# SCH_PicoPU_MoBo_2025-06-30.net
KiCad netlist of a schematic drawn in EasyEDA
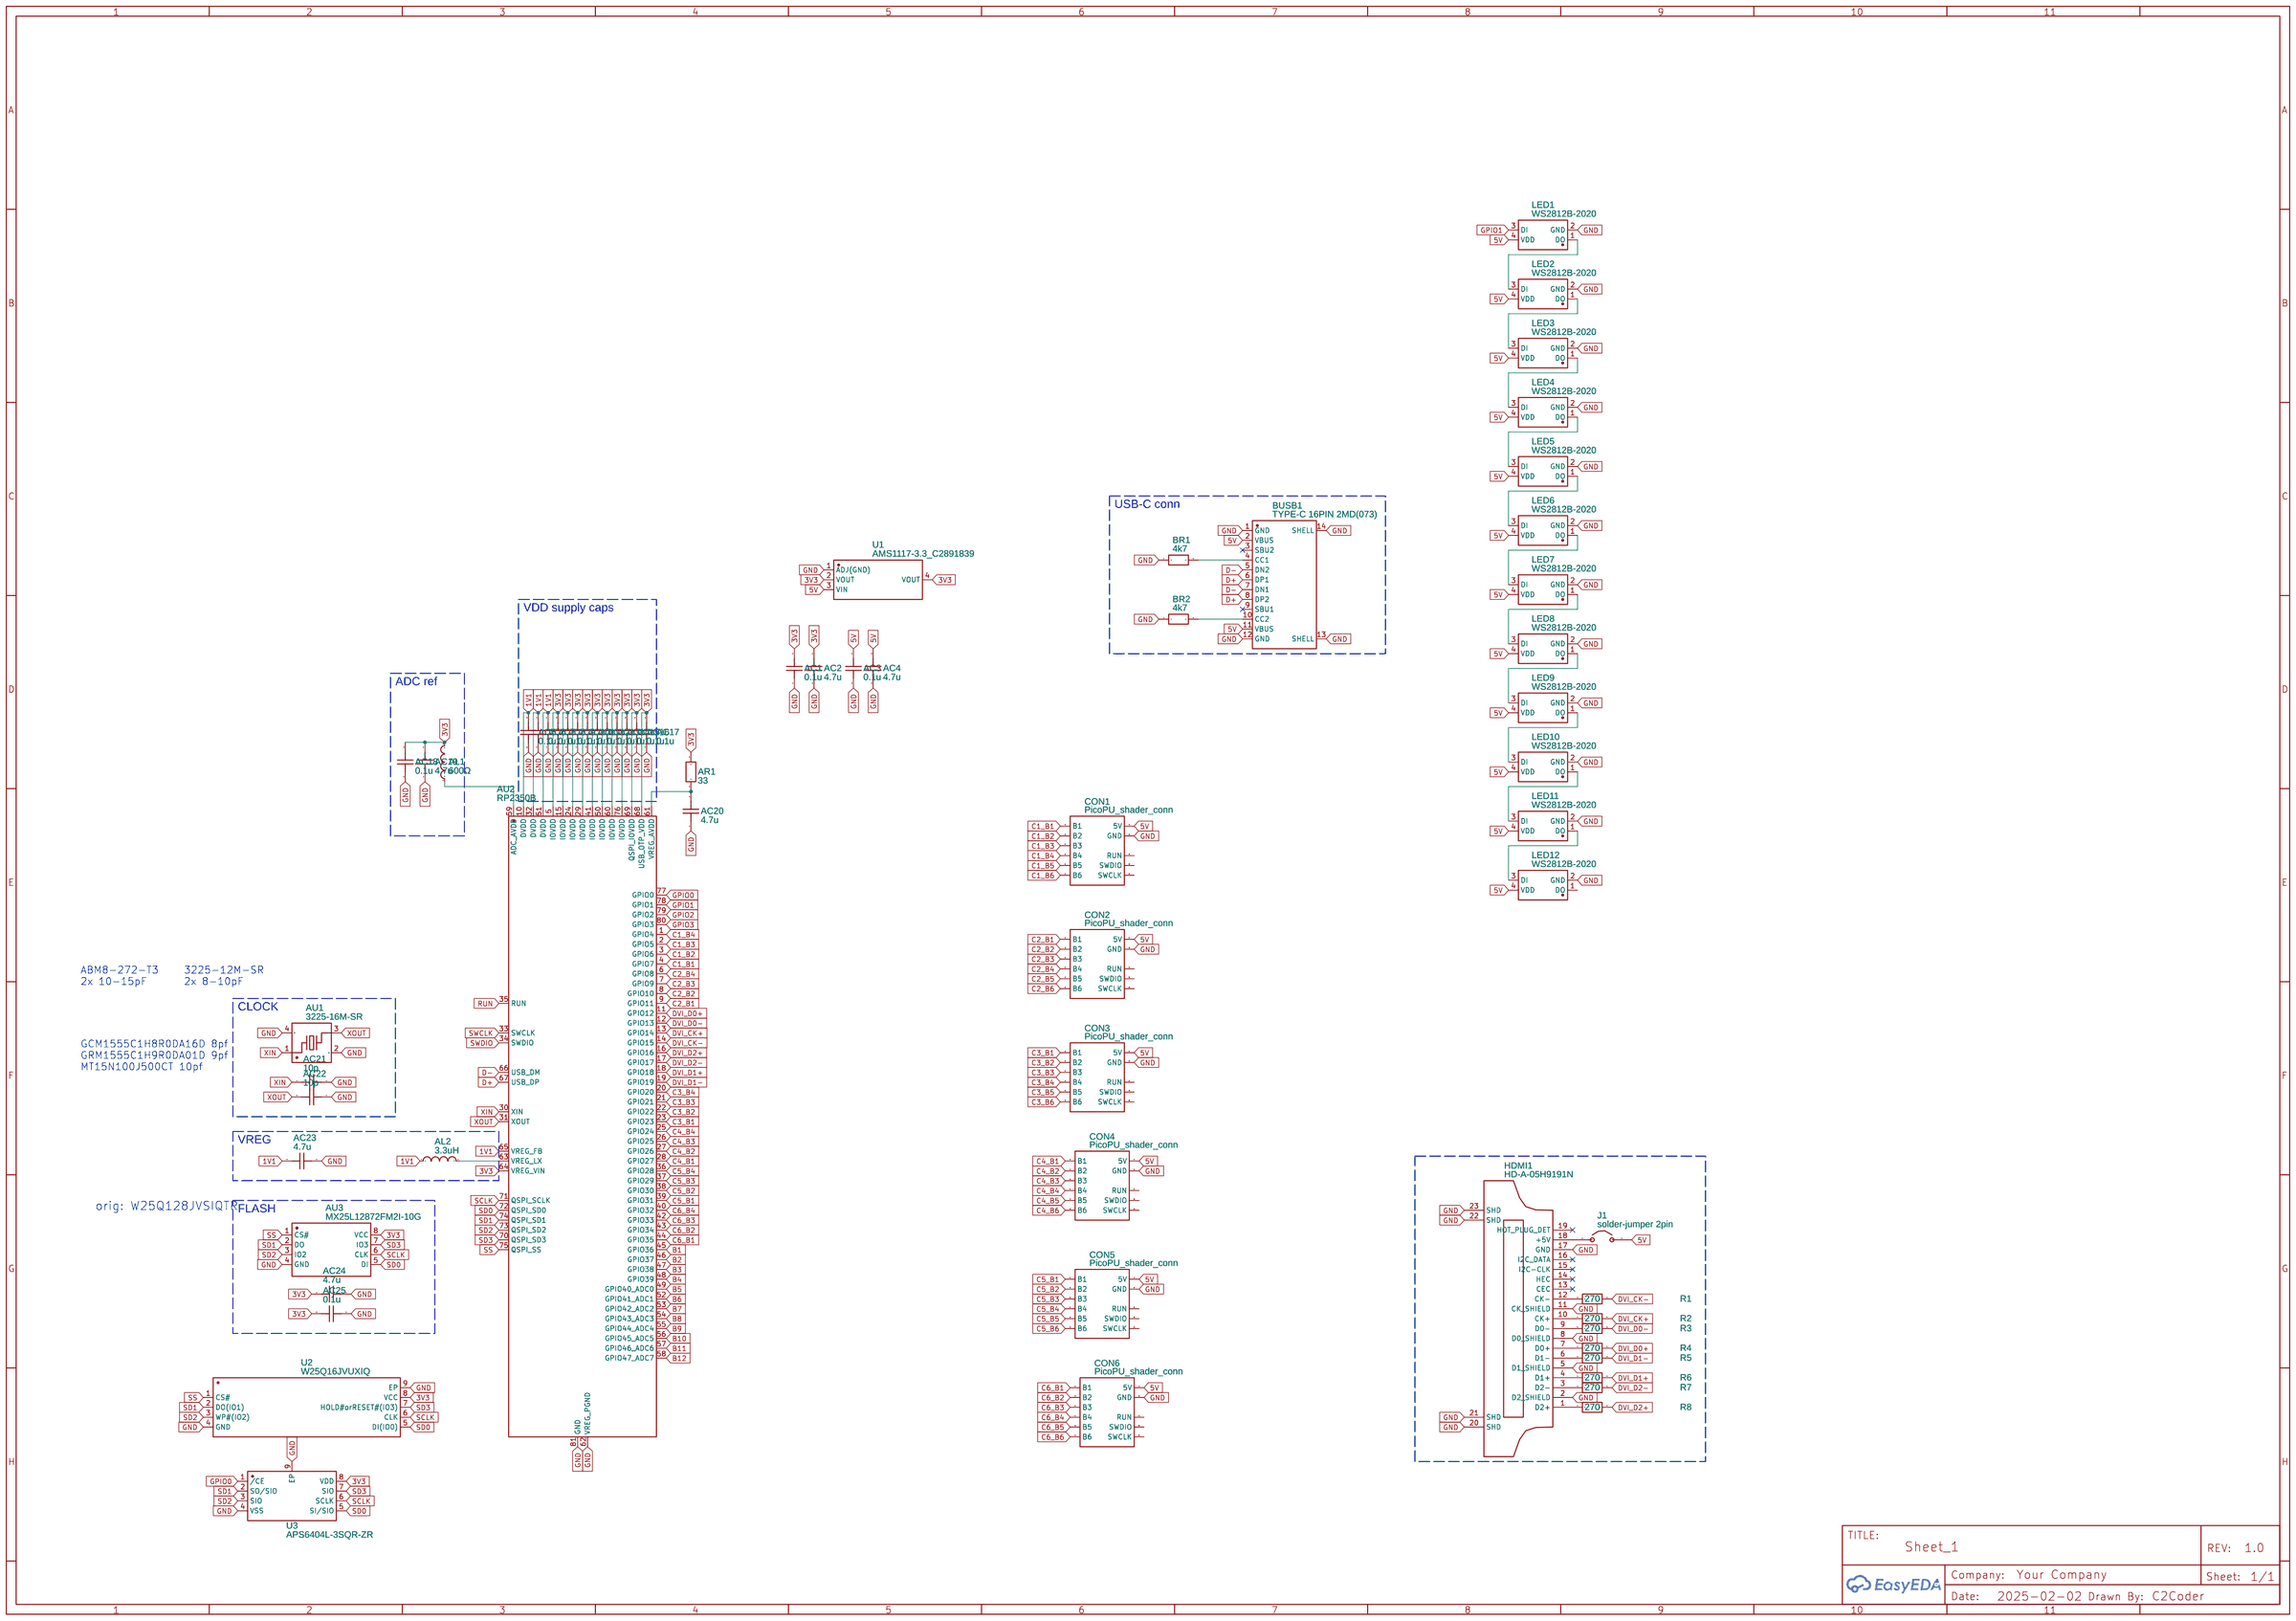
[diagram p0: schematic sheet]

(export (version "E")
  (design (tool "Eeschema 10.0.6"))
  (components
    (comp (ref "AC1")
      (value "0.1u")
      (fields (field (name "Manufacturer Part") "CL05B104KP5NNNC") (field (name "Manufacturer") "SAMSUNG"))
      (libsource (lib "") (part "C_0402_US"))
    )
    (comp (ref "AC2")
      (value "4.7u")
      (fields (field (name "Manufacturer Part") "0603X475K100CT") (field (name "Manufacturer") "WALSIN"))
      (libsource (lib "") (part "C_0402_US"))
    )
    (comp (ref "AC3")
      (value "0.1u")
      (fields (field (name "Manufacturer Part") "CL05B104KP5NNNC") (field (name "Manufacturer") "SAMSUNG"))
      (libsource (lib "") (part "C_0402_US"))
    )
    (comp (ref "AC4")
      (value "4.7u")
      (fields (field (name "Manufacturer Part") "0603X475K100CT") (field (name "Manufacturer") "WALSIN"))
      (libsource (lib "") (part "C_0402_US"))
    )
    (comp (ref "AC5")
      (value "0.1u")
      (fields (field (name "Manufacturer Part") "CL05B104KP5NNNC") (field (name "Manufacturer") "SAMSUNG"))
      (libsource (lib "") (part "C_0402_US"))
    )
    (comp (ref "AC6")
      (value "0.1u")
      (fields (field (name "Manufacturer Part") "CL05B104KP5NNNC") (field (name "Manufacturer") "SAMSUNG"))
      (libsource (lib "") (part "C_0402_US"))
    )
    (comp (ref "AC7")
      (value "0.1u")
      (fields (field (name "Manufacturer Part") "CL05B104KP5NNNC") (field (name "Manufacturer") "SAMSUNG"))
      (libsource (lib "") (part "C_0402_US"))
    )
    (comp (ref "AC8")
      (value "0.1u")
      (fields (field (name "Manufacturer Part") "CL05B104KP5NNNC") (field (name "Manufacturer") "SAMSUNG"))
      (libsource (lib "") (part "C_0402_US"))
    )
    (comp (ref "AC9")
      (value "0.1u")
      (fields (field (name "Manufacturer Part") "CL05B104KP5NNNC") (field (name "Manufacturer") "SAMSUNG"))
      (libsource (lib "") (part "C_0402_US"))
    )
    (comp (ref "AC10")
      (value "0.1u")
      (fields (field (name "Manufacturer Part") "CL05B104KP5NNNC") (field (name "Manufacturer") "SAMSUNG"))
      (libsource (lib "") (part "C_0402_US"))
    )
    (comp (ref "AC11")
      (value "0.1u")
      (fields (field (name "Manufacturer Part") "CL05B104KP5NNNC") (field (name "Manufacturer") "SAMSUNG"))
      (libsource (lib "") (part "C_0402_US"))
    )
    (comp (ref "AC12")
      (value "0.1u")
      (fields (field (name "Manufacturer Part") "CL05B104KP5NNNC") (field (name "Manufacturer") "SAMSUNG"))
      (libsource (lib "") (part "C_0402_US"))
    )
    (comp (ref "AC13")
      (value "0.1u")
      (fields (field (name "Manufacturer Part") "CL05B104KP5NNNC") (field (name "Manufacturer") "SAMSUNG"))
      (libsource (lib "") (part "C_0402_US"))
    )
    (comp (ref "AC14")
      (value "0.1u")
      (fields (field (name "Manufacturer Part") "CL05B104KP5NNNC") (field (name "Manufacturer") "SAMSUNG"))
      (libsource (lib "") (part "C_0402_US"))
    )
    (comp (ref "AC15")
      (value "0.1u")
      (fields (field (name "Manufacturer Part") "CL05B104KP5NNNC") (field (name "Manufacturer") "SAMSUNG"))
      (libsource (lib "") (part "C_0402_US"))
    )
    (comp (ref "AC16")
      (value "0.1u")
      (fields (field (name "Manufacturer Part") "CL05B104KP5NNNC") (field (name "Manufacturer") "SAMSUNG"))
      (libsource (lib "") (part "C_0402_US"))
    )
    (comp (ref "AC17")
      (value "0.1u")
      (fields (field (name "Manufacturer Part") "CL05B104KP5NNNC") (field (name "Manufacturer") "SAMSUNG"))
      (libsource (lib "") (part "C_0402_US"))
    )
    (comp (ref "AC18")
      (value "0.1u")
      (fields (field (name "Manufacturer Part") "CL05B104KP5NNNC") (field (name "Manufacturer") "SAMSUNG"))
      (libsource (lib "") (part "C_0402_US"))
    )
    (comp (ref "AC19")
      (value "4.7u")
      (fields (field (name "Manufacturer Part") "0603X475K100CT") (field (name "Manufacturer") "WALSIN"))
      (libsource (lib "") (part "C_0402_US"))
    )
    (comp (ref "AC20")
      (value "4.7u")
      (fields (field (name "Manufacturer Part") "0603X475K100CT") (field (name "Manufacturer") "WALSIN"))
      (libsource (lib "") (part "C_0402_US"))
    )
    (comp (ref "AC21")
      (value "10p")
      (fields (field (name "Manufacturer Part") "MT15N100J500CT") (field (name "Manufacturer") "WALSIN"))
      (libsource (lib "") (part "C_0402_US_1"))
    )
    (comp (ref "AC22")
      (value "10p")
      (fields (field (name "Manufacturer Part") "MT15N100J500CT") (field (name "Manufacturer") "WALSIN"))
      (libsource (lib "") (part "C_0402_US_1"))
    )
    (comp (ref "AC23")
      (value "4.7u")
      (fields (field (name "Manufacturer Part") "0603X475K100CT") (field (name "Manufacturer") "WALSIN"))
      (libsource (lib "") (part "C_0402_US_1"))
    )
    (comp (ref "AC24")
      (value "4.7u")
      (fields (field (name "Manufacturer Part") "0603X475K100CT") (field (name "Manufacturer") "WALSIN"))
      (libsource (lib "") (part "C_0402_US_1"))
    )
    (comp (ref "AC25")
      (value "0.1u")
      (fields (field (name "Manufacturer Part") "CL05B104KP5NNNC") (field (name "Manufacturer") "SAMSUNG"))
      (libsource (lib "") (part "C_0402_US_1"))
    )
    (comp (ref "AL1")
      (value "600Ω")
      (fields (field (name "Manufacturer Part") "BLM18HE601SN1D") (field (name "Manufacturer") "muRata"))
      (libsource (lib "") (part "BLM18HE601SN1D"))
    )
    (comp (ref "AL2")
      (value "3.3uH")
      (fields (field (name "Manufacturer Part") "LQM2HPN3R3MG0L") (field (name "Manufacturer") "MURATA"))
      (libsource (lib "") (part "AOTA-B201610S3R3-101-T"))
    )
    (comp (ref "AR1")
      (value "33")
      (fields (field (name "Manufacturer Part") "HP02WAF330JTCE") (field (name "Manufacturer") "ROYALOHM"))
      (libsource (lib "") (part "R_0402_EU_2"))
    )
    (comp (ref "AU1")
      (value "3225-16M-SR")
      (fields (field (name "Manufacturer") "SR Passives"))
      (libsource (lib "") (part "3225-16M-SR"))
    )
    (comp (ref "AU2") (value "RP2350B") (libsource (lib "") (part "RP2350B")))
    (comp (ref "AU3")
      (value "MX25L12872FM2I-10G")
      (fields (field (name "Manufacturer Part") "AT25SF081B-SSHD-T") (field (name "Manufacturer") "RENESAS"))
      (libsource (lib "") (part "W25Q128JVSIQTR"))
    )
    (comp (ref "BR1")
      (value "4k7")
      (fields (field (name "Manufacturer Part") "HP02WAF4701TCE") (field (name "Manufacturer") "ROYALOHM"))
      (libsource (lib "") (part "R_0402_EU_1"))
    )
    (comp (ref "BR2")
      (value "4k7")
      (fields (field (name "Manufacturer Part") "HP02WAF4701TCE") (field (name "Manufacturer") "ROYALOHM"))
      (libsource (lib "") (part "R_0402_EU_1"))
    )
    (comp (ref "BUSB1")
      (value "TYPE-C 16PIN 2MD(073)")
      (fields (field (name "Manufacturer Part") "USB4215-03-A") (field (name "Manufacturer") "GCT"))
      (libsource (lib "") (part "TYPE-C 16PIN 2MD(073)"))
    )
    (comp (ref "CON1") (value "PicoPU_shader_conn") (libsource (lib "") (part "PicoPU_shader_conn")))
    (comp (ref "CON2") (value "PicoPU_shader_conn") (libsource (lib "") (part "PicoPU_shader_conn")))
    (comp (ref "CON3") (value "PicoPU_shader_conn") (libsource (lib "") (part "PicoPU_shader_conn")))
    (comp (ref "CON4") (value "PicoPU_shader_conn") (libsource (lib "") (part "PicoPU_shader_conn")))
    (comp (ref "CON5") (value "PicoPU_shader_conn") (libsource (lib "") (part "PicoPU_shader_conn")))
    (comp (ref "CON6") (value "PicoPU_shader_conn") (libsource (lib "") (part "PicoPU_shader_conn")))
    (comp (ref "HDMI1")
      (value "HD-A-05H9191N")
      (fields (field (name "Manufacturer") "HanElectricity(瀚源)"))
      (libsource (lib "") (part "HD-A-05H9191N"))
    )
    (comp (ref "J1") (value "solder-jumper 2pin") (libsource (lib "") (part "solder-jumper 2pin")))
    (comp (ref "LED1")
      (value "WS2812B-2020")
      (fields (field (name "Manufacturer") "worldsemi"))
      (libsource (lib "") (part "WS2812B-2020"))
    )
    (comp (ref "LED2")
      (value "WS2812B-2020")
      (fields (field (name "Manufacturer") "worldsemi"))
      (libsource (lib "") (part "WS2812B-2020"))
    )
    (comp (ref "LED3")
      (value "WS2812B-2020")
      (fields (field (name "Manufacturer") "worldsemi"))
      (libsource (lib "") (part "WS2812B-2020"))
    )
    (comp (ref "LED4")
      (value "WS2812B-2020")
      (fields (field (name "Manufacturer") "worldsemi"))
      (libsource (lib "") (part "WS2812B-2020"))
    )
    (comp (ref "LED5")
      (value "WS2812B-2020")
      (fields (field (name "Manufacturer") "worldsemi"))
      (libsource (lib "") (part "WS2812B-2020"))
    )
    (comp (ref "LED6")
      (value "WS2812B-2020")
      (fields (field (name "Manufacturer") "worldsemi"))
      (libsource (lib "") (part "WS2812B-2020"))
    )
    (comp (ref "LED7")
      (value "WS2812B-2020")
      (fields (field (name "Manufacturer") "worldsemi"))
      (libsource (lib "") (part "WS2812B-2020"))
    )
    (comp (ref "LED8")
      (value "WS2812B-2020")
      (fields (field (name "Manufacturer") "worldsemi"))
      (libsource (lib "") (part "WS2812B-2020"))
    )
    (comp (ref "LED9")
      (value "WS2812B-2020")
      (fields (field (name "Manufacturer") "worldsemi"))
      (libsource (lib "") (part "WS2812B-2020"))
    )
    (comp (ref "LED10")
      (value "WS2812B-2020")
      (fields (field (name "Manufacturer") "worldsemi"))
      (libsource (lib "") (part "WS2812B-2020"))
    )
    (comp (ref "LED11")
      (value "WS2812B-2020")
      (fields (field (name "Manufacturer") "worldsemi"))
      (libsource (lib "") (part "WS2812B-2020"))
    )
    (comp (ref "LED12")
      (value "WS2812B-2020")
      (fields (field (name "Manufacturer") "worldsemi"))
      (libsource (lib "") (part "WS2812B-2020"))
    )
    (comp (ref "R1") (value "270") (libsource (lib "") (part "R_0402_EU")))
    (comp (ref "R2") (value "270") (libsource (lib "") (part "R_0402_EU")))
    (comp (ref "R3") (value "270") (libsource (lib "") (part "R_0402_EU")))
    (comp (ref "R4") (value "270") (libsource (lib "") (part "R_0402_EU")))
    (comp (ref "R5") (value "270") (libsource (lib "") (part "R_0402_EU")))
    (comp (ref "R6") (value "270") (libsource (lib "") (part "R_0402_EU")))
    (comp (ref "R7") (value "270") (libsource (lib "") (part "R_0402_EU")))
    (comp (ref "R8") (value "270") (libsource (lib "") (part "R_0402_EU")))
    (comp (ref "U1")
      (value "AMS1117-3.3_C2891839")
      (fields (field (name "Manufacturer Part") "AMS1117-3.3") (field (name "Manufacturer") "YONGYUTAI(永裕泰)"))
      (libsource (lib "") (part "AMS1117-3.3_C2891839"))
    )
    (comp (ref "U2")
      (value "W25Q16JVUXIQ")
      (fields (field (name "Manufacturer") "WINBOND(华邦)"))
      (libsource (lib "") (part "W25Q16JVUXIQ"))
    )
    (comp (ref "U3")
      (value "APS6404L-3SQR-ZR")
      (fields (field (name "Manufacturer") "Apmemory"))
      (libsource (lib "") (part "APS6404L-3SQR-ZR"))
    )
  )
  (nets
    (net (code "1") (name "1V1") (class "Default")
      (node (ref "AC23") (pin "2") (pinfunction "2_2") (pintype "unspecified"))
      (node (ref "AC5") (pin "2") (pinfunction "2_2") (pintype "unspecified"))
      (node (ref "AC6") (pin "2") (pinfunction "2_2") (pintype "unspecified"))
      (node (ref "AC7") (pin "2") (pinfunction "2_2") (pintype "unspecified"))
      (node (ref "AL2") (pin "1") (pinfunction "1_1") (pintype "unspecified"))
      (node (ref "AU2") (pin "10") (pinfunction "DVDD_10") (pintype "unspecified"))
      (node (ref "AU2") (pin "32") (pinfunction "DVDD_32") (pintype "unspecified"))
      (node (ref "AU2") (pin "51") (pinfunction "DVDD_51") (pintype "unspecified"))
      (node (ref "AU2") (pin "65") (pinfunction "VREG_FB_65") (pintype "unspecified"))
    )
    (net (code "2") (name "3V3") (class "Default")
      (node (ref "AC1") (pin "2") (pinfunction "2_2") (pintype "unspecified"))
      (node (ref "AC10") (pin "2") (pinfunction "2_2") (pintype "unspecified"))
      (node (ref "AC11") (pin "2") (pinfunction "2_2") (pintype "unspecified"))
      (node (ref "AC12") (pin "2") (pinfunction "2_2") (pintype "unspecified"))
      (node (ref "AC13") (pin "2") (pinfunction "2_2") (pintype "unspecified"))
      (node (ref "AC14") (pin "2") (pinfunction "2_2") (pintype "unspecified"))
      (node (ref "AC15") (pin "2") (pinfunction "2_2") (pintype "unspecified"))
      (node (ref "AC16") (pin "2") (pinfunction "2_2") (pintype "unspecified"))
      (node (ref "AC17") (pin "2") (pinfunction "2_2") (pintype "unspecified"))
      (node (ref "AC18") (pin "2") (pinfunction "2_2") (pintype "unspecified"))
      (node (ref "AC19") (pin "2") (pinfunction "2_2") (pintype "unspecified"))
      (node (ref "AC2") (pin "2") (pinfunction "2_2") (pintype "unspecified"))
      (node (ref "AC24") (pin "2") (pinfunction "2_2") (pintype "unspecified"))
      (node (ref "AC25") (pin "2") (pinfunction "2_2") (pintype "unspecified"))
      (node (ref "AC8") (pin "2") (pinfunction "2_2") (pintype "unspecified"))
      (node (ref "AC9") (pin "2") (pinfunction "2_2") (pintype "unspecified"))
      (node (ref "AL1") (pin "2") (pinfunction "2_2") (pintype "unspecified"))
      (node (ref "AR1") (pin "2") (pinfunction "2_2") (pintype "unspecified"))
      (node (ref "AU2") (pin "15") (pinfunction "IOVDD_15") (pintype "unspecified"))
      (node (ref "AU2") (pin "24") (pinfunction "IOVDD_24") (pintype "unspecified"))
      (node (ref "AU2") (pin "29") (pinfunction "IOVDD_29") (pintype "unspecified"))
      (node (ref "AU2") (pin "41") (pinfunction "IOVDD_41") (pintype "unspecified"))
      (node (ref "AU2") (pin "5") (pinfunction "IOVDD_5") (pintype "unspecified"))
      (node (ref "AU2") (pin "50") (pinfunction "IOVDD_50") (pintype "unspecified"))
      (node (ref "AU2") (pin "60") (pinfunction "IOVDD_60") (pintype "unspecified"))
      (node (ref "AU2") (pin "64") (pinfunction "VREG_VIN_64") (pintype "unspecified"))
      (node (ref "AU2") (pin "68") (pinfunction "USB_OTP_VDD_68") (pintype "unspecified"))
      (node (ref "AU2") (pin "69") (pinfunction "QSPI_IOVDD_69") (pintype "unspecified"))
      (node (ref "AU2") (pin "76") (pinfunction "IOVDD_76") (pintype "unspecified"))
      (node (ref "AU3") (pin "8") (pinfunction "VCC_8") (pintype "unspecified"))
      (node (ref "U1") (pin "2") (pinfunction "VOUT_2") (pintype "unspecified"))
      (node (ref "U1") (pin "4") (pinfunction "VOUT_4") (pintype "unspecified"))
      (node (ref "U2") (pin "8") (pinfunction "VCC_8") (pintype "unspecified"))
      (node (ref "U3") (pin "8") (pinfunction "VDD_8") (pintype "unspecified"))
    )
    (net (code "3") (name "5V") (class "Default")
      (node (ref "AC3") (pin "2") (pinfunction "2_2") (pintype "unspecified"))
      (node (ref "AC4") (pin "2") (pinfunction "2_2") (pintype "unspecified"))
      (node (ref "BUSB1") (pin "11") (pinfunction "VBUS_11") (pintype "unspecified"))
      (node (ref "BUSB1") (pin "2") (pinfunction "VBUS_2") (pintype "unspecified"))
      (node (ref "CON1") (pin "5V") (pinfunction "5V_5V") (pintype "unspecified"))
      (node (ref "CON2") (pin "5V") (pinfunction "5V_5V") (pintype "unspecified"))
      (node (ref "CON3") (pin "5V") (pinfunction "5V_5V") (pintype "unspecified"))
      (node (ref "CON4") (pin "5V") (pinfunction "5V_5V") (pintype "unspecified"))
      (node (ref "CON5") (pin "5V") (pinfunction "5V_5V") (pintype "unspecified"))
      (node (ref "CON6") (pin "5V") (pinfunction "5V_5V") (pintype "unspecified"))
      (node (ref "J1") (pin "2") (pinfunction "2_2") (pintype "unspecified"))
      (node (ref "LED1") (pin "4") (pinfunction "VDD_4") (pintype "unspecified"))
      (node (ref "LED10") (pin "4") (pinfunction "VDD_4") (pintype "unspecified"))
      (node (ref "LED11") (pin "4") (pinfunction "VDD_4") (pintype "unspecified"))
      (node (ref "LED12") (pin "4") (pinfunction "VDD_4") (pintype "unspecified"))
      (node (ref "LED2") (pin "4") (pinfunction "VDD_4") (pintype "unspecified"))
      (node (ref "LED3") (pin "4") (pinfunction "VDD_4") (pintype "unspecified"))
      (node (ref "LED4") (pin "4") (pinfunction "VDD_4") (pintype "unspecified"))
      (node (ref "LED5") (pin "4") (pinfunction "VDD_4") (pintype "unspecified"))
      (node (ref "LED6") (pin "4") (pinfunction "VDD_4") (pintype "unspecified"))
      (node (ref "LED7") (pin "4") (pinfunction "VDD_4") (pintype "unspecified"))
      (node (ref "LED8") (pin "4") (pinfunction "VDD_4") (pintype "unspecified"))
      (node (ref "LED9") (pin "4") (pinfunction "VDD_4") (pintype "unspecified"))
      (node (ref "U1") (pin "3") (pinfunction "VIN_3") (pintype "unspecified"))
    )
    (net (code "4") (name "B1") (class "Default")
      (node (ref "AU2") (pin "45") (pinfunction "GPIO36_45") (pintype "unspecified"))
    )
    (net (code "5") (name "B2") (class "Default")
      (node (ref "AU2") (pin "46") (pinfunction "GPIO37_46") (pintype "unspecified"))
    )
    (net (code "6") (name "B3") (class "Default")
      (node (ref "AU2") (pin "47") (pinfunction "GPIO38_47") (pintype "unspecified"))
    )
    (net (code "7") (name "B4") (class "Default")
      (node (ref "AU2") (pin "48") (pinfunction "GPIO39_48") (pintype "unspecified"))
    )
    (net (code "8") (name "B5") (class "Default")
      (node (ref "AU2") (pin "49") (pinfunction "GPIO40_ADC0_49") (pintype "unspecified"))
    )
    (net (code "9") (name "B6") (class "Default")
      (node (ref "AU2") (pin "52") (pinfunction "GPIO41_ADC1_52") (pintype "unspecified"))
    )
    (net (code "10") (name "B7") (class "Default")
      (node (ref "AU2") (pin "53") (pinfunction "GPIO42_ADC2_53") (pintype "unspecified"))
    )
    (net (code "11") (name "B8") (class "Default")
      (node (ref "AU2") (pin "54") (pinfunction "GPIO43_ADC3_54") (pintype "unspecified"))
    )
    (net (code "12") (name "B9") (class "Default")
      (node (ref "AU2") (pin "55") (pinfunction "GPIO44_ADC4_55") (pintype "unspecified"))
    )
    (net (code "13") (name "B10") (class "Default")
      (node (ref "AU2") (pin "56") (pinfunction "GPIO45_ADC5_56") (pintype "unspecified"))
    )
    (net (code "14") (name "B11") (class "Default")
      (node (ref "AU2") (pin "57") (pinfunction "GPIO46_ADC6_57") (pintype "unspecified"))
    )
    (net (code "15") (name "B12") (class "Default")
      (node (ref "AU2") (pin "58") (pinfunction "GPIO47_ADC7_58") (pintype "unspecified"))
    )
    (net (code "16") (name "C1_B1") (class "Default")
      (node (ref "AU2") (pin "4") (pinfunction "GPIO7_4") (pintype "unspecified"))
      (node (ref "CON1") (pin "B1") (pinfunction "B1_B1") (pintype "unspecified"))
    )
    (net (code "17") (name "C1_B2") (class "Default")
      (node (ref "AU2") (pin "3") (pinfunction "GPIO6_3") (pintype "unspecified"))
      (node (ref "CON1") (pin "B2") (pinfunction "B2_B2") (pintype "unspecified"))
    )
    (net (code "18") (name "C1_B3") (class "Default")
      (node (ref "AU2") (pin "2") (pinfunction "GPIO5_2") (pintype "unspecified"))
      (node (ref "CON1") (pin "B3") (pinfunction "B3_B3") (pintype "unspecified"))
    )
    (net (code "19") (name "C1_B4") (class "Default")
      (node (ref "AU2") (pin "1") (pinfunction "GPIO4_1") (pintype "unspecified"))
      (node (ref "CON1") (pin "B4") (pinfunction "B4_B4") (pintype "unspecified"))
    )
    (net (code "20") (name "C1_B5") (class "Default")
      (node (ref "CON1") (pin "B5") (pinfunction "B5_B5") (pintype "unspecified"))
    )
    (net (code "21") (name "C1_B6") (class "Default")
      (node (ref "CON1") (pin "B6") (pinfunction "B6_B6") (pintype "unspecified"))
    )
    (net (code "22") (name "C2_B1") (class "Default")
      (node (ref "AU2") (pin "9") (pinfunction "GPIO11_9") (pintype "unspecified"))
      (node (ref "CON2") (pin "B1") (pinfunction "B1_B1") (pintype "unspecified"))
    )
    (net (code "23") (name "C2_B2") (class "Default")
      (node (ref "AU2") (pin "8") (pinfunction "GPIO10_8") (pintype "unspecified"))
      (node (ref "CON2") (pin "B2") (pinfunction "B2_B2") (pintype "unspecified"))
    )
    (net (code "24") (name "C2_B3") (class "Default")
      (node (ref "AU2") (pin "7") (pinfunction "GPIO9_7") (pintype "unspecified"))
      (node (ref "CON2") (pin "B3") (pinfunction "B3_B3") (pintype "unspecified"))
    )
    (net (code "25") (name "C2_B4") (class "Default")
      (node (ref "AU2") (pin "6") (pinfunction "GPIO8_6") (pintype "unspecified"))
      (node (ref "CON2") (pin "B4") (pinfunction "B4_B4") (pintype "unspecified"))
    )
    (net (code "26") (name "C2_B5") (class "Default")
      (node (ref "CON2") (pin "B5") (pinfunction "B5_B5") (pintype "unspecified"))
    )
    (net (code "27") (name "C2_B6") (class "Default")
      (node (ref "CON2") (pin "B6") (pinfunction "B6_B6") (pintype "unspecified"))
    )
    (net (code "28") (name "C3_B1") (class "Default")
      (node (ref "AU2") (pin "23") (pinfunction "GPIO23_23") (pintype "unspecified"))
      (node (ref "CON3") (pin "B1") (pinfunction "B1_B1") (pintype "unspecified"))
    )
    (net (code "29") (name "C3_B2") (class "Default")
      (node (ref "AU2") (pin "22") (pinfunction "GPIO22_22") (pintype "unspecified"))
      (node (ref "CON3") (pin "B2") (pinfunction "B2_B2") (pintype "unspecified"))
    )
    (net (code "30") (name "C3_B3") (class "Default")
      (node (ref "AU2") (pin "21") (pinfunction "GPIO21_21") (pintype "unspecified"))
      (node (ref "CON3") (pin "B3") (pinfunction "B3_B3") (pintype "unspecified"))
    )
    (net (code "31") (name "C3_B4") (class "Default")
      (node (ref "AU2") (pin "20") (pinfunction "GPIO20_20") (pintype "unspecified"))
      (node (ref "CON3") (pin "B4") (pinfunction "B4_B4") (pintype "unspecified"))
    )
    (net (code "32") (name "C3_B5") (class "Default")
      (node (ref "CON3") (pin "B5") (pinfunction "B5_B5") (pintype "unspecified"))
    )
    (net (code "33") (name "C3_B6") (class "Default")
      (node (ref "CON3") (pin "B6") (pinfunction "B6_B6") (pintype "unspecified"))
    )
    (net (code "34") (name "C4_B1") (class "Default")
      (node (ref "AU2") (pin "28") (pinfunction "GPIO27_28") (pintype "unspecified"))
      (node (ref "CON4") (pin "B1") (pinfunction "B1_B1") (pintype "unspecified"))
    )
    (net (code "35") (name "C4_B2") (class "Default")
      (node (ref "AU2") (pin "27") (pinfunction "GPIO26_27") (pintype "unspecified"))
      (node (ref "CON4") (pin "B2") (pinfunction "B2_B2") (pintype "unspecified"))
    )
    (net (code "36") (name "C4_B3") (class "Default")
      (node (ref "AU2") (pin "26") (pinfunction "GPIO25_26") (pintype "unspecified"))
      (node (ref "CON4") (pin "B3") (pinfunction "B3_B3") (pintype "unspecified"))
    )
    (net (code "37") (name "C4_B4") (class "Default")
      (node (ref "AU2") (pin "25") (pinfunction "GPIO24_25") (pintype "unspecified"))
      (node (ref "CON4") (pin "B4") (pinfunction "B4_B4") (pintype "unspecified"))
    )
    (net (code "38") (name "C4_B5") (class "Default")
      (node (ref "CON4") (pin "B5") (pinfunction "B5_B5") (pintype "unspecified"))
    )
    (net (code "39") (name "C4_B6") (class "Default")
      (node (ref "CON4") (pin "B6") (pinfunction "B6_B6") (pintype "unspecified"))
    )
    (net (code "40") (name "C5_B1") (class "Default")
      (node (ref "AU2") (pin "39") (pinfunction "GPIO31_39") (pintype "unspecified"))
      (node (ref "CON5") (pin "B1") (pinfunction "B1_B1") (pintype "unspecified"))
    )
    (net (code "41") (name "C5_B2") (class "Default")
      (node (ref "AU2") (pin "38") (pinfunction "GPIO30_38") (pintype "unspecified"))
      (node (ref "CON5") (pin "B2") (pinfunction "B2_B2") (pintype "unspecified"))
    )
    (net (code "42") (name "C5_B3") (class "Default")
      (node (ref "AU2") (pin "37") (pinfunction "GPIO29_37") (pintype "unspecified"))
      (node (ref "CON5") (pin "B3") (pinfunction "B3_B3") (pintype "unspecified"))
    )
    (net (code "43") (name "C5_B4") (class "Default")
      (node (ref "AU2") (pin "36") (pinfunction "GPIO28_36") (pintype "unspecified"))
      (node (ref "CON5") (pin "B4") (pinfunction "B4_B4") (pintype "unspecified"))
    )
    (net (code "44") (name "C5_B5") (class "Default")
      (node (ref "CON5") (pin "B5") (pinfunction "B5_B5") (pintype "unspecified"))
    )
    (net (code "45") (name "C5_B6") (class "Default")
      (node (ref "CON5") (pin "B6") (pinfunction "B6_B6") (pintype "unspecified"))
    )
    (net (code "46") (name "C6_B1") (class "Default")
      (node (ref "AU2") (pin "44") (pinfunction "GPIO35_44") (pintype "unspecified"))
      (node (ref "CON6") (pin "B1") (pinfunction "B1_B1") (pintype "unspecified"))
    )
    (net (code "47") (name "C6_B2") (class "Default")
      (node (ref "AU2") (pin "43") (pinfunction "GPIO34_43") (pintype "unspecified"))
      (node (ref "CON6") (pin "B2") (pinfunction "B2_B2") (pintype "unspecified"))
    )
    (net (code "48") (name "C6_B3") (class "Default")
      (node (ref "AU2") (pin "42") (pinfunction "GPIO33_42") (pintype "unspecified"))
      (node (ref "CON6") (pin "B3") (pinfunction "B3_B3") (pintype "unspecified"))
    )
    (net (code "49") (name "C6_B4") (class "Default")
      (node (ref "AU2") (pin "40") (pinfunction "GPIO32_40") (pintype "unspecified"))
      (node (ref "CON6") (pin "B4") (pinfunction "B4_B4") (pintype "unspecified"))
    )
    (net (code "50") (name "C6_B5") (class "Default")
      (node (ref "CON6") (pin "B5") (pinfunction "B5_B5") (pintype "unspecified"))
    )
    (net (code "51") (name "C6_B6") (class "Default")
      (node (ref "CON6") (pin "B6") (pinfunction "B6_B6") (pintype "unspecified"))
    )
    (net (code "52") (name "D+") (class "Default")
      (node (ref "AU2") (pin "67") (pinfunction "USB_DP_67") (pintype "unspecified"))
      (node (ref "BUSB1") (pin "6") (pinfunction "DP1_6") (pintype "unspecified"))
      (node (ref "BUSB1") (pin "8") (pinfunction "DP2_8") (pintype "unspecified"))
    )
    (net (code "53") (name "D-") (class "Default")
      (node (ref "AU2") (pin "66") (pinfunction "USB_DM_66") (pintype "unspecified"))
      (node (ref "BUSB1") (pin "5") (pinfunction "DN2_5") (pintype "unspecified"))
      (node (ref "BUSB1") (pin "7") (pinfunction "DN1_7") (pintype "unspecified"))
    )
    (net (code "54") (name "DVI_CK+") (class "Default")
      (node (ref "AU2") (pin "13") (pinfunction "GPIO14_13") (pintype "unspecified"))
      (node (ref "R2") (pin "2") (pinfunction "2_2") (pintype "unspecified"))
    )
    (net (code "55") (name "DVI_CK-") (class "Default")
      (node (ref "AU2") (pin "14") (pinfunction "GPIO15_14") (pintype "unspecified"))
      (node (ref "R1") (pin "2") (pinfunction "2_2") (pintype "unspecified"))
    )
    (net (code "56") (name "DVI_D0+") (class "Default")
      (node (ref "AU2") (pin "11") (pinfunction "GPIO12_11") (pintype "unspecified"))
      (node (ref "R4") (pin "2") (pinfunction "2_2") (pintype "unspecified"))
    )
    (net (code "57") (name "DVI_D0-") (class "Default")
      (node (ref "AU2") (pin "12") (pinfunction "GPIO13_12") (pintype "unspecified"))
      (node (ref "R3") (pin "2") (pinfunction "2_2") (pintype "unspecified"))
    )
    (net (code "58") (name "DVI_D1+") (class "Default")
      (node (ref "AU2") (pin "18") (pinfunction "GPIO18_18") (pintype "unspecified"))
      (node (ref "R6") (pin "2") (pinfunction "2_2") (pintype "unspecified"))
    )
    (net (code "59") (name "DVI_D1-") (class "Default")
      (node (ref "AU2") (pin "19") (pinfunction "GPIO19_19") (pintype "unspecified"))
      (node (ref "R5") (pin "2") (pinfunction "2_2") (pintype "unspecified"))
    )
    (net (code "60") (name "DVI_D2+") (class "Default")
      (node (ref "AU2") (pin "16") (pinfunction "GPIO16_16") (pintype "unspecified"))
      (node (ref "R8") (pin "2") (pinfunction "2_2") (pintype "unspecified"))
    )
    (net (code "61") (name "DVI_D2-") (class "Default")
      (node (ref "AU2") (pin "17") (pinfunction "GPIO17_17") (pintype "unspecified"))
      (node (ref "R7") (pin "2") (pinfunction "2_2") (pintype "unspecified"))
    )
    (net (code "62") (name "GND") (class "Default")
      (node (ref "AC1") (pin "1") (pinfunction "1_1") (pintype "unspecified"))
      (node (ref "AC10") (pin "1") (pinfunction "1_1") (pintype "unspecified"))
      (node (ref "AC11") (pin "1") (pinfunction "1_1") (pintype "unspecified"))
      (node (ref "AC12") (pin "1") (pinfunction "1_1") (pintype "unspecified"))
      (node (ref "AC13") (pin "1") (pinfunction "1_1") (pintype "unspecified"))
      (node (ref "AC14") (pin "1") (pinfunction "1_1") (pintype "unspecified"))
      (node (ref "AC15") (pin "1") (pinfunction "1_1") (pintype "unspecified"))
      (node (ref "AC16") (pin "1") (pinfunction "1_1") (pintype "unspecified"))
      (node (ref "AC17") (pin "1") (pinfunction "1_1") (pintype "unspecified"))
      (node (ref "AC18") (pin "1") (pinfunction "1_1") (pintype "unspecified"))
      (node (ref "AC19") (pin "1") (pinfunction "1_1") (pintype "unspecified"))
      (node (ref "AC2") (pin "1") (pinfunction "1_1") (pintype "unspecified"))
      (node (ref "AC20") (pin "1") (pinfunction "1_1") (pintype "unspecified"))
      (node (ref "AC21") (pin "1") (pinfunction "1_1") (pintype "unspecified"))
      (node (ref "AC22") (pin "1") (pinfunction "1_1") (pintype "unspecified"))
      (node (ref "AC23") (pin "1") (pinfunction "1_1") (pintype "unspecified"))
      (node (ref "AC24") (pin "1") (pinfunction "1_1") (pintype "unspecified"))
      (node (ref "AC25") (pin "1") (pinfunction "1_1") (pintype "unspecified"))
      (node (ref "AC3") (pin "1") (pinfunction "1_1") (pintype "unspecified"))
      (node (ref "AC4") (pin "1") (pinfunction "1_1") (pintype "unspecified"))
      (node (ref "AC5") (pin "1") (pinfunction "1_1") (pintype "unspecified"))
      (node (ref "AC6") (pin "1") (pinfunction "1_1") (pintype "unspecified"))
      (node (ref "AC7") (pin "1") (pinfunction "1_1") (pintype "unspecified"))
      (node (ref "AC8") (pin "1") (pinfunction "1_1") (pintype "unspecified"))
      (node (ref "AC9") (pin "1") (pinfunction "1_1") (pintype "unspecified"))
      (node (ref "AU1") (pin "2") (pinfunction "GND_2") (pintype "input"))
      (node (ref "AU1") (pin "4") (pinfunction "GND_4") (pintype "input"))
      (node (ref "AU2") (pin "62") (pinfunction "VREG_PGND_62") (pintype "unspecified"))
      (node (ref "AU2") (pin "81") (pinfunction "GND_81") (pintype "unspecified"))
      (node (ref "AU3") (pin "4") (pinfunction "GND_4") (pintype "unspecified"))
      (node (ref "BR1") (pin "1") (pinfunction "1_1") (pintype "unspecified"))
      (node (ref "BR2") (pin "1") (pinfunction "1_1") (pintype "unspecified"))
      (node (ref "BUSB1") (pin "1") (pinfunction "GND_1") (pintype "unspecified"))
      (node (ref "BUSB1") (pin "12") (pinfunction "GND_12") (pintype "unspecified"))
      (node (ref "BUSB1") (pin "13") (pinfunction "SHELL_13") (pintype "unspecified"))
      (node (ref "BUSB1") (pin "14") (pinfunction "SHELL_14") (pintype "unspecified"))
      (node (ref "CON1") (pin "GND") (pinfunction "GND_GND") (pintype "unspecified"))
      (node (ref "CON2") (pin "GND") (pinfunction "GND_GND") (pintype "unspecified"))
      (node (ref "CON3") (pin "GND") (pinfunction "GND_GND") (pintype "unspecified"))
      (node (ref "CON4") (pin "GND") (pinfunction "GND_GND") (pintype "unspecified"))
      (node (ref "CON5") (pin "GND") (pinfunction "GND_GND") (pintype "unspecified"))
      (node (ref "CON6") (pin "GND") (pinfunction "GND_GND") (pintype "unspecified"))
      (node (ref "HDMI1") (pin "11") (pinfunction "CK_SHIELD_11") (pintype "unspecified"))
      (node (ref "HDMI1") (pin "17") (pinfunction "GND_17") (pintype "unspecified"))
      (node (ref "HDMI1") (pin "2") (pinfunction "D2_SHIELD_2") (pintype "unspecified"))
      (node (ref "HDMI1") (pin "20") (pinfunction "SHD_20") (pintype "unspecified"))
      (node (ref "HDMI1") (pin "21") (pinfunction "SHD_21") (pintype "unspecified"))
      (node (ref "HDMI1") (pin "22") (pinfunction "SHD_22") (pintype "unspecified"))
      (node (ref "HDMI1") (pin "23") (pinfunction "SHD_23") (pintype "unspecified"))
      (node (ref "HDMI1") (pin "5") (pinfunction "D1_SHIELD_5") (pintype "unspecified"))
      (node (ref "HDMI1") (pin "8") (pinfunction "D0_SHIELD_8") (pintype "unspecified"))
      (node (ref "LED1") (pin "2") (pinfunction "GND_2") (pintype "unspecified"))
      (node (ref "LED10") (pin "2") (pinfunction "GND_2") (pintype "unspecified"))
      (node (ref "LED11") (pin "2") (pinfunction "GND_2") (pintype "unspecified"))
      (node (ref "LED12") (pin "2") (pinfunction "GND_2") (pintype "unspecified"))
      (node (ref "LED2") (pin "2") (pinfunction "GND_2") (pintype "unspecified"))
      (node (ref "LED3") (pin "2") (pinfunction "GND_2") (pintype "unspecified"))
      (node (ref "LED4") (pin "2") (pinfunction "GND_2") (pintype "unspecified"))
      (node (ref "LED5") (pin "2") (pinfunction "GND_2") (pintype "unspecified"))
      (node (ref "LED6") (pin "2") (pinfunction "GND_2") (pintype "unspecified"))
      (node (ref "LED7") (pin "2") (pinfunction "GND_2") (pintype "unspecified"))
      (node (ref "LED8") (pin "2") (pinfunction "GND_2") (pintype "unspecified"))
      (node (ref "LED9") (pin "2") (pinfunction "GND_2") (pintype "unspecified"))
      (node (ref "U1") (pin "1") (pinfunction "ADJ(GND)_1") (pintype "unspecified"))
      (node (ref "U2") (pin "4") (pinfunction "GND_4") (pintype "unspecified"))
      (node (ref "U2") (pin "9") (pinfunction "EP_9") (pintype "unspecified"))
      (node (ref "U3") (pin "4") (pinfunction "VSS_4") (pintype "unspecified"))
      (node (ref "U3") (pin "9") (pinfunction "EP_9") (pintype "unspecified"))
    )
    (net (code "63") (name "GPIO0") (class "Default")
      (node (ref "AU2") (pin "77") (pinfunction "GPIO0_77") (pintype "unspecified"))
      (node (ref "U3") (pin "1") (pinfunction "/CE_1") (pintype "unspecified"))
    )
    (net (code "64") (name "GPIO1") (class "Default")
      (node (ref "AU2") (pin "78") (pinfunction "GPIO1_78") (pintype "unspecified"))
      (node (ref "LED1") (pin "3") (pinfunction "DI_3") (pintype "unspecified"))
    )
    (net (code "65") (name "GPIO2") (class "Default")
      (node (ref "AU2") (pin "79") (pinfunction "GPIO2_79") (pintype "unspecified"))
    )
    (net (code "66") (name "GPIO3") (class "Default")
      (node (ref "AU2") (pin "80") (pinfunction "GPIO3_80") (pintype "unspecified"))
    )
    (net (code "67") (name "Net-(AU2-ADC_AVDD)") (class "Default")
      (node (ref "AL1") (pin "1") (pinfunction "1_1") (pintype "unspecified"))
      (node (ref "AU2") (pin "59") (pinfunction "ADC_AVDD_59") (pintype "unspecified"))
    )
    (net (code "68") (name "Net-(AU2-VREG_AVDD)") (class "Default")
      (node (ref "AC20") (pin "2") (pinfunction "2_2") (pintype "unspecified"))
      (node (ref "AR1") (pin "1") (pinfunction "1_1") (pintype "unspecified"))
      (node (ref "AU2") (pin "61") (pinfunction "VREG_AVDD_61") (pintype "unspecified"))
    )
    (net (code "69") (name "Net-(AU2-VREG_LX)") (class "Default")
      (node (ref "AL2") (pin "2") (pinfunction "2_2") (pintype "unspecified"))
      (node (ref "AU2") (pin "63") (pinfunction "VREG_LX_63") (pintype "unspecified"))
    )
    (net (code "70") (name "Net-(BUSB1-CC1)") (class "Default")
      (node (ref "BR1") (pin "2") (pinfunction "2_2") (pintype "unspecified"))
      (node (ref "BUSB1") (pin "4") (pinfunction "CC1_4") (pintype "unspecified"))
    )
    (net (code "71") (name "Net-(BUSB1-CC2)") (class "Default")
      (node (ref "BR2") (pin "2") (pinfunction "2_2") (pintype "unspecified"))
      (node (ref "BUSB1") (pin "10") (pinfunction "CC2_10") (pintype "unspecified"))
    )
    (net (code "72") (name "Net-(HDMI1-+5V)") (class "Default")
      (node (ref "HDMI1") (pin "18") (pinfunction "+5V_18") (pintype "unspecified"))
      (node (ref "J1") (pin "1") (pinfunction "1_1") (pintype "unspecified"))
    )
    (net (code "73") (name "Net-(HDMI1-CK+)") (class "Default")
      (node (ref "HDMI1") (pin "10") (pinfunction "CK+_10") (pintype "unspecified"))
      (node (ref "R2") (pin "1") (pinfunction "1_1") (pintype "unspecified"))
    )
    (net (code "74") (name "Net-(HDMI1-CK-)") (class "Default")
      (node (ref "HDMI1") (pin "12") (pinfunction "CK-_12") (pintype "unspecified"))
      (node (ref "R1") (pin "1") (pinfunction "1_1") (pintype "unspecified"))
    )
    (net (code "75") (name "Net-(HDMI1-D0+)") (class "Default")
      (node (ref "HDMI1") (pin "7") (pinfunction "D0+_7") (pintype "unspecified"))
      (node (ref "R4") (pin "1") (pinfunction "1_1") (pintype "unspecified"))
    )
    (net (code "76") (name "Net-(HDMI1-D0-)") (class "Default")
      (node (ref "HDMI1") (pin "9") (pinfunction "D0-_9") (pintype "unspecified"))
      (node (ref "R3") (pin "1") (pinfunction "1_1") (pintype "unspecified"))
    )
    (net (code "77") (name "Net-(HDMI1-D1+)") (class "Default")
      (node (ref "HDMI1") (pin "4") (pinfunction "D1+_4") (pintype "unspecified"))
      (node (ref "R6") (pin "1") (pinfunction "1_1") (pintype "unspecified"))
    )
    (net (code "78") (name "Net-(HDMI1-D1-)") (class "Default")
      (node (ref "HDMI1") (pin "6") (pinfunction "D1-_6") (pintype "unspecified"))
      (node (ref "R5") (pin "1") (pinfunction "1_1") (pintype "unspecified"))
    )
    (net (code "79") (name "Net-(HDMI1-D2+)") (class "Default")
      (node (ref "HDMI1") (pin "1") (pinfunction "D2+_1") (pintype "unspecified"))
      (node (ref "R8") (pin "1") (pinfunction "1_1") (pintype "unspecified"))
    )
    (net (code "80") (name "Net-(HDMI1-D2-)") (class "Default")
      (node (ref "HDMI1") (pin "3") (pinfunction "D2-_3") (pintype "unspecified"))
      (node (ref "R7") (pin "1") (pinfunction "1_1") (pintype "unspecified"))
    )
    (net (code "81") (name "Net-(LED1-DO)") (class "Default")
      (node (ref "LED1") (pin "1") (pinfunction "DO_1") (pintype "unspecified"))
      (node (ref "LED2") (pin "3") (pinfunction "DI_3") (pintype "unspecified"))
    )
    (net (code "82") (name "Net-(LED2-DO)") (class "Default")
      (node (ref "LED2") (pin "1") (pinfunction "DO_1") (pintype "unspecified"))
      (node (ref "LED3") (pin "3") (pinfunction "DI_3") (pintype "unspecified"))
    )
    (net (code "83") (name "Net-(LED3-DO)") (class "Default")
      (node (ref "LED3") (pin "1") (pinfunction "DO_1") (pintype "unspecified"))
      (node (ref "LED4") (pin "3") (pinfunction "DI_3") (pintype "unspecified"))
    )
    (net (code "84") (name "Net-(LED4-DO)") (class "Default")
      (node (ref "LED4") (pin "1") (pinfunction "DO_1") (pintype "unspecified"))
      (node (ref "LED5") (pin "3") (pinfunction "DI_3") (pintype "unspecified"))
    )
    (net (code "85") (name "Net-(LED5-DO)") (class "Default")
      (node (ref "LED5") (pin "1") (pinfunction "DO_1") (pintype "unspecified"))
      (node (ref "LED6") (pin "3") (pinfunction "DI_3") (pintype "unspecified"))
    )
    (net (code "86") (name "Net-(LED6-DO)") (class "Default")
      (node (ref "LED6") (pin "1") (pinfunction "DO_1") (pintype "unspecified"))
      (node (ref "LED7") (pin "3") (pinfunction "DI_3") (pintype "unspecified"))
    )
    (net (code "87") (name "Net-(LED7-DO)") (class "Default")
      (node (ref "LED7") (pin "1") (pinfunction "DO_1") (pintype "unspecified"))
      (node (ref "LED8") (pin "3") (pinfunction "DI_3") (pintype "unspecified"))
    )
    (net (code "88") (name "Net-(LED8-DO)") (class "Default")
      (node (ref "LED8") (pin "1") (pinfunction "DO_1") (pintype "unspecified"))
      (node (ref "LED9") (pin "3") (pinfunction "DI_3") (pintype "unspecified"))
    )
    (net (code "89") (name "Net-(LED10-DI)") (class "Default")
      (node (ref "LED10") (pin "3") (pinfunction "DI_3") (pintype "unspecified"))
      (node (ref "LED9") (pin "1") (pinfunction "DO_1") (pintype "unspecified"))
    )
    (net (code "90") (name "Net-(LED10-DO)") (class "Default")
      (node (ref "LED10") (pin "1") (pinfunction "DO_1") (pintype "unspecified"))
      (node (ref "LED11") (pin "3") (pinfunction "DI_3") (pintype "unspecified"))
    )
    (net (code "91") (name "Net-(LED11-DO)") (class "Default")
      (node (ref "LED11") (pin "1") (pinfunction "DO_1") (pintype "unspecified"))
      (node (ref "LED12") (pin "3") (pinfunction "DI_3") (pintype "unspecified"))
    )
    (net (code "92") (name "RUN") (class "Default")
      (node (ref "AU2") (pin "35") (pinfunction "RUN_35") (pintype "unspecified"))
    )
    (net (code "93") (name "SCLK") (class "Default")
      (node (ref "AU2") (pin "71") (pinfunction "QSPI_SCLK_71") (pintype "unspecified"))
      (node (ref "AU3") (pin "6") (pinfunction "CLK_6") (pintype "unspecified"))
      (node (ref "U2") (pin "6") (pinfunction "CLK_6") (pintype "unspecified"))
      (node (ref "U3") (pin "6") (pinfunction "SCLK_6") (pintype "unspecified"))
    )
    (net (code "94") (name "SD0") (class "Default")
      (node (ref "AU2") (pin "72") (pinfunction "QSPI_SD0_72") (pintype "unspecified"))
      (node (ref "AU3") (pin "5") (pinfunction "DI_5") (pintype "unspecified"))
      (node (ref "U2") (pin "5") (pinfunction "DI(IO0)_5") (pintype "unspecified"))
      (node (ref "U3") (pin "5") (pinfunction "SI/SIO_5") (pintype "unspecified"))
    )
    (net (code "95") (name "SD1") (class "Default")
      (node (ref "AU2") (pin "74") (pinfunction "QSPI_SD1_74") (pintype "unspecified"))
      (node (ref "AU3") (pin "2") (pinfunction "DO_2") (pintype "unspecified"))
      (node (ref "U2") (pin "2") (pinfunction "DO(IO1)_2") (pintype "unspecified"))
      (node (ref "U3") (pin "2") (pinfunction "SO/SIO_2") (pintype "unspecified"))
    )
    (net (code "96") (name "SD2") (class "Default")
      (node (ref "AU2") (pin "73") (pinfunction "QSPI_SD2_73") (pintype "unspecified"))
      (node (ref "AU3") (pin "3") (pinfunction "IO2_3") (pintype "unspecified"))
      (node (ref "U2") (pin "3") (pinfunction "WP#(IO2)_3") (pintype "unspecified"))
      (node (ref "U3") (pin "3") (pinfunction "SIO_3") (pintype "unspecified"))
    )
    (net (code "97") (name "SD3") (class "Default")
      (node (ref "AU2") (pin "70") (pinfunction "QSPI_SD3_70") (pintype "unspecified"))
      (node (ref "AU3") (pin "7") (pinfunction "IO3_7") (pintype "unspecified"))
      (node (ref "U2") (pin "7") (pinfunction "HOLD#orRESET#(IO3)_7") (pintype "unspecified"))
      (node (ref "U3") (pin "7") (pinfunction "SIO_7") (pintype "unspecified"))
    )
    (net (code "98") (name "SS") (class "Default")
      (node (ref "AU2") (pin "75") (pinfunction "QSPI_SS_75") (pintype "unspecified"))
      (node (ref "AU3") (pin "1") (pinfunction "CS#_1") (pintype "unspecified"))
      (node (ref "U2") (pin "1") (pinfunction "CS#_1") (pintype "unspecified"))
    )
    (net (code "99") (name "SWCLK") (class "Default")
      (node (ref "AU2") (pin "33") (pinfunction "SWCLK_33") (pintype "unspecified"))
    )
    (net (code "100") (name "SWDIO") (class "Default")
      (node (ref "AU2") (pin "34") (pinfunction "SWDIO_34") (pintype "unspecified"))
    )
    (net (code "101") (name "XIN") (class "Default")
      (node (ref "AC21") (pin "2") (pinfunction "2_2") (pintype "unspecified"))
      (node (ref "AU1") (pin "1") (pinfunction "1_1") (pintype "input"))
      (node (ref "AU2") (pin "30") (pinfunction "XIN_30") (pintype "unspecified"))
    )
    (net (code "102") (name "XOUT") (class "Default")
      (node (ref "AC22") (pin "2") (pinfunction "2_2") (pintype "unspecified"))
      (node (ref "AU1") (pin "3") (pinfunction "3_3") (pintype "input"))
      (node (ref "AU2") (pin "31") (pinfunction "XOUT_31") (pintype "unspecified"))
    )
    (net (code "103") (name "unconnected-(BUSB1-SBU1-Pad9)") (class "Default")
      (node (ref "BUSB1") (pin "9") (pinfunction "SBU1_9") (pintype "unspecified+no_connect"))
    )
    (net (code "104") (name "unconnected-(BUSB1-SBU2-Pad3)") (class "Default")
      (node (ref "BUSB1") (pin "3") (pinfunction "SBU2_3") (pintype "unspecified+no_connect"))
    )
    (net (code "105") (name "unconnected-(CON1-PadRUN)") (class "Default")
      (node (ref "CON1") (pin "RUN") (pinfunction "RUN_RUN") (pintype "unspecified"))
    )
    (net (code "106") (name "unconnected-(CON1-PadSWCLK)") (class "Default")
      (node (ref "CON1") (pin "SWCLK") (pinfunction "SWCLK_SWCLK") (pintype "unspecified"))
    )
    (net (code "107") (name "unconnected-(CON1-PadSWDIO)") (class "Default")
      (node (ref "CON1") (pin "SWDIO") (pinfunction "SWDIO_SWDIO") (pintype "unspecified"))
    )
    (net (code "108") (name "unconnected-(CON2-PadRUN)") (class "Default")
      (node (ref "CON2") (pin "RUN") (pinfunction "RUN_RUN") (pintype "unspecified"))
    )
    (net (code "109") (name "unconnected-(CON2-PadSWCLK)") (class "Default")
      (node (ref "CON2") (pin "SWCLK") (pinfunction "SWCLK_SWCLK") (pintype "unspecified"))
    )
    (net (code "110") (name "unconnected-(CON2-PadSWDIO)") (class "Default")
      (node (ref "CON2") (pin "SWDIO") (pinfunction "SWDIO_SWDIO") (pintype "unspecified"))
    )
    (net (code "111") (name "unconnected-(CON3-PadRUN)") (class "Default")
      (node (ref "CON3") (pin "RUN") (pinfunction "RUN_RUN") (pintype "unspecified"))
    )
    (net (code "112") (name "unconnected-(CON3-PadSWCLK)") (class "Default")
      (node (ref "CON3") (pin "SWCLK") (pinfunction "SWCLK_SWCLK") (pintype "unspecified"))
    )
    (net (code "113") (name "unconnected-(CON3-PadSWDIO)") (class "Default")
      (node (ref "CON3") (pin "SWDIO") (pinfunction "SWDIO_SWDIO") (pintype "unspecified"))
    )
    (net (code "114") (name "unconnected-(CON4-PadRUN)") (class "Default")
      (node (ref "CON4") (pin "RUN") (pinfunction "RUN_RUN") (pintype "unspecified"))
    )
    (net (code "115") (name "unconnected-(CON4-PadSWCLK)") (class "Default")
      (node (ref "CON4") (pin "SWCLK") (pinfunction "SWCLK_SWCLK") (pintype "unspecified"))
    )
    (net (code "116") (name "unconnected-(CON4-PadSWDIO)") (class "Default")
      (node (ref "CON4") (pin "SWDIO") (pinfunction "SWDIO_SWDIO") (pintype "unspecified"))
    )
    (net (code "117") (name "unconnected-(CON5-PadRUN)") (class "Default")
      (node (ref "CON5") (pin "RUN") (pinfunction "RUN_RUN") (pintype "unspecified"))
    )
    (net (code "118") (name "unconnected-(CON5-PadSWCLK)") (class "Default")
      (node (ref "CON5") (pin "SWCLK") (pinfunction "SWCLK_SWCLK") (pintype "unspecified"))
    )
    (net (code "119") (name "unconnected-(CON5-PadSWDIO)") (class "Default")
      (node (ref "CON5") (pin "SWDIO") (pinfunction "SWDIO_SWDIO") (pintype "unspecified"))
    )
    (net (code "120") (name "unconnected-(CON6-PadRUN)") (class "Default")
      (node (ref "CON6") (pin "RUN") (pinfunction "RUN_RUN") (pintype "unspecified"))
    )
    (net (code "121") (name "unconnected-(CON6-PadSWCLK)") (class "Default")
      (node (ref "CON6") (pin "SWCLK") (pinfunction "SWCLK_SWCLK") (pintype "unspecified"))
    )
    (net (code "122") (name "unconnected-(CON6-PadSWDIO)") (class "Default")
      (node (ref "CON6") (pin "SWDIO") (pinfunction "SWDIO_SWDIO") (pintype "unspecified"))
    )
    (net (code "123") (name "unconnected-(HDMI1-CEC-Pad13)") (class "Default")
      (node (ref "HDMI1") (pin "13") (pinfunction "CEC_13") (pintype "unspecified+no_connect"))
    )
    (net (code "124") (name "unconnected-(HDMI1-HEC-Pad14)") (class "Default")
      (node (ref "HDMI1") (pin "14") (pinfunction "HEC_14") (pintype "unspecified+no_connect"))
    )
    (net (code "125") (name "unconnected-(HDMI1-HOT_PLUG_DET-Pad19)") (class "Default")
      (node (ref "HDMI1") (pin "19") (pinfunction "HOT_PLUG_DET_19") (pintype "unspecified+no_connect"))
    )
    (net (code "126") (name "unconnected-(HDMI1-I2C-CLK-Pad15)") (class "Default")
      (node (ref "HDMI1") (pin "15") (pinfunction "I2C-CLK_15") (pintype "unspecified+no_connect"))
    )
    (net (code "127") (name "unconnected-(HDMI1-I2C_DATA-Pad16)") (class "Default")
      (node (ref "HDMI1") (pin "16") (pinfunction "I2C_DATA_16") (pintype "unspecified+no_connect"))
    )
    (net (code "128") (name "unconnected-(LED12-DO-Pad1)") (class "Default")
      (node (ref "LED12") (pin "1") (pinfunction "DO_1") (pintype "unspecified"))
    )
  )
)
